# ext.net
KiCad netlist of a schematic drawn in EAGLE
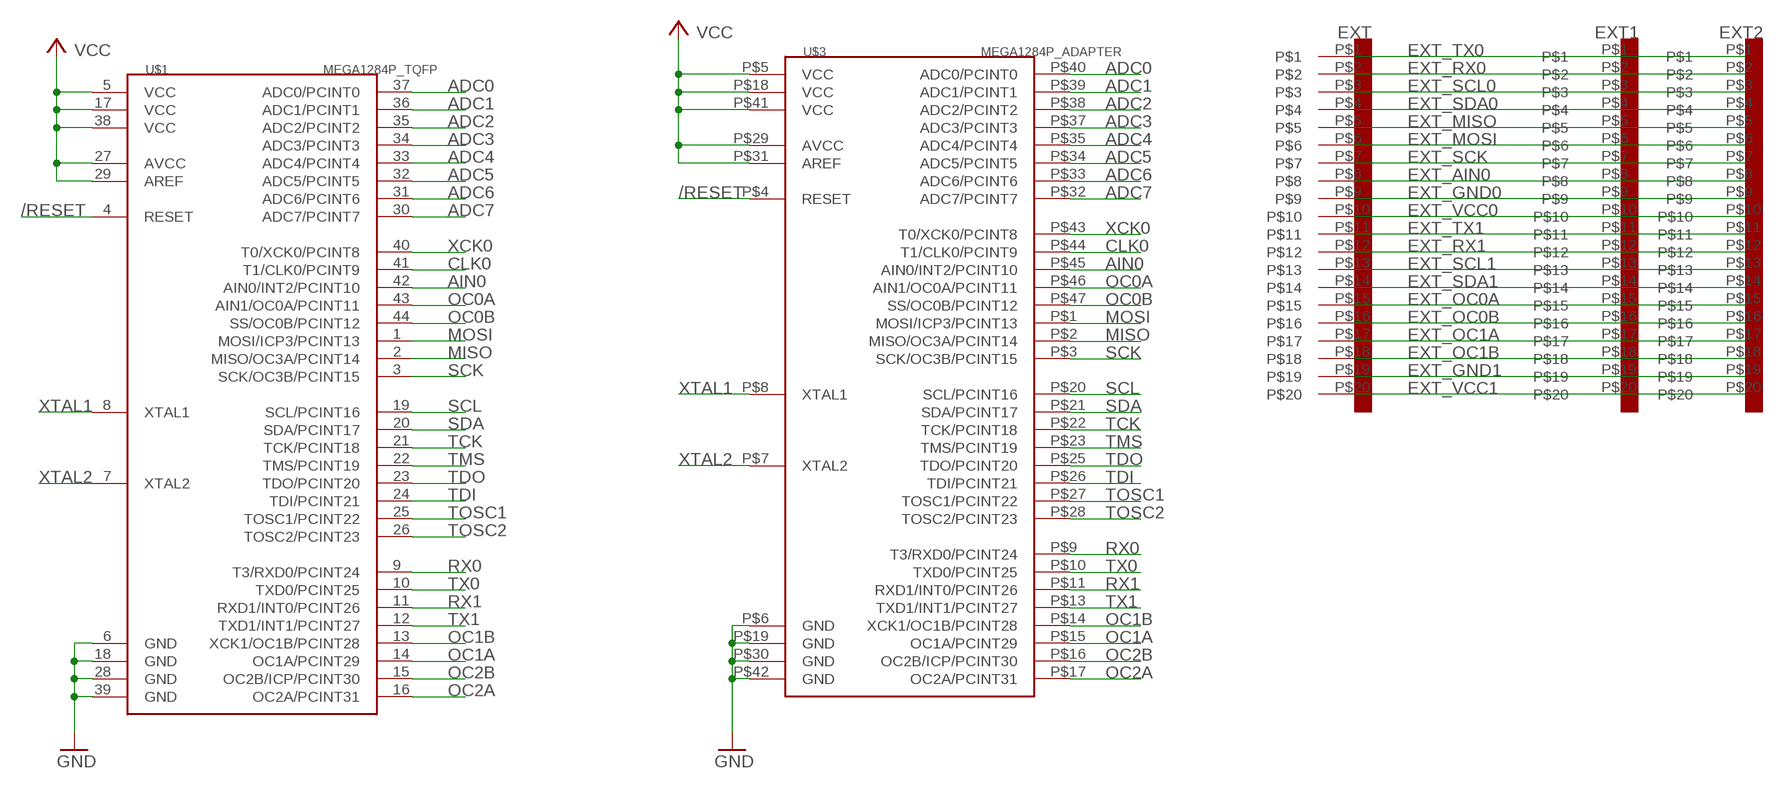
[diagram p0: schematic, sheet 1]

(export (version "E")
  (design (tool "Eeschema 10.0.6"))
  (components
    (comp (ref "EXT")
      (value "CON_DIL_20")
      (footprint "eagle-import:CON_DIL_20")
      (libsource (lib "eagle-import") (part "CON_DIL_20"))
    )
    (comp (ref "EXT1")
      (value "CON_DIL_20")
      (footprint "eagle-import:CON_DIL_20")
      (libsource (lib "eagle-import") (part "CON_DIL_20"))
    )
    (comp (ref "EXT2")
      (value "CON_DIL_20")
      (footprint "eagle-import:CON_DIL_20")
      (libsource (lib "eagle-import") (part "CON_DIL_20"))
    )
    (comp (ref "U$1")
      (value "MEGA1284P_TQFP")
      (footprint "eagle-import:TQFP44")
      (libsource (lib "eagle-import") (part "MEGA1284P_TQFP"))
    )
    (comp (ref "U$3")
      (value "MEGA1284P_ADAPTER")
      (footprint "eagle-import:TQFP44-ADAPTER")
      (libsource (lib "eagle-import") (part "MEGA1284P_ADAPTER"))
    )
  )
  (nets
    (net (code "1") (name "ADC0") (class "Default")
      (node (ref "U$1") (pin "37") (pinfunction "ADC0/PCINT0_37") (pintype "bidirectional"))
      (node (ref "U$3") (pin "P$40") (pinfunction "ADC0/PCINT0_P$40") (pintype "bidirectional"))
    )
    (net (code "2") (name "ADC1") (class "Default")
      (node (ref "U$1") (pin "36") (pinfunction "ADC1/PCINT1_36") (pintype "bidirectional"))
      (node (ref "U$3") (pin "P$39") (pinfunction "ADC1/PCINT1_P$39") (pintype "bidirectional"))
    )
    (net (code "3") (name "ADC2") (class "Default")
      (node (ref "U$1") (pin "35") (pinfunction "ADC2/PCINT2_35") (pintype "bidirectional"))
      (node (ref "U$3") (pin "P$38") (pinfunction "ADC2/PCINT2_P$38") (pintype "bidirectional"))
    )
    (net (code "4") (name "ADC3") (class "Default")
      (node (ref "U$1") (pin "34") (pinfunction "ADC3/PCINT3_34") (pintype "bidirectional"))
      (node (ref "U$3") (pin "P$37") (pinfunction "ADC3/PCINT3_P$37") (pintype "bidirectional"))
    )
    (net (code "5") (name "ADC4") (class "Default")
      (node (ref "U$1") (pin "33") (pinfunction "ADC4/PCINT4_33") (pintype "bidirectional"))
      (node (ref "U$3") (pin "P$35") (pinfunction "ADC4/PCINT4_P$35") (pintype "bidirectional"))
    )
    (net (code "6") (name "ADC5") (class "Default")
      (node (ref "U$1") (pin "32") (pinfunction "ADC5/PCINT5_32") (pintype "bidirectional"))
      (node (ref "U$3") (pin "P$34") (pinfunction "ADC5/PCINT5_P$34") (pintype "bidirectional"))
    )
    (net (code "7") (name "ADC6") (class "Default")
      (node (ref "U$1") (pin "31") (pinfunction "ADC6/PCINT6_31") (pintype "bidirectional"))
      (node (ref "U$3") (pin "P$33") (pinfunction "ADC6/PCINT6_P$33") (pintype "bidirectional"))
    )
    (net (code "8") (name "ADC7") (class "Default")
      (node (ref "U$1") (pin "30") (pinfunction "ADC7/PCINT7_30") (pintype "bidirectional"))
      (node (ref "U$3") (pin "P$32") (pinfunction "ADC7/PCINT7_P$32") (pintype "bidirectional"))
    )
    (net (code "9") (name "AIN0") (class "Default")
      (node (ref "U$1") (pin "42") (pinfunction "AIN0/INT2/PCINT10_42") (pintype "bidirectional"))
      (node (ref "U$3") (pin "P$45") (pinfunction "AIN0/INT2/PCINT10_P$45") (pintype "bidirectional"))
    )
    (net (code "10") (name "CLK0") (class "Default")
      (node (ref "U$1") (pin "41") (pinfunction "T1/CLK0/PCINT9_41") (pintype "bidirectional"))
      (node (ref "U$3") (pin "P$44") (pinfunction "T1/CLK0/PCINT9_P$44") (pintype "bidirectional"))
    )
    (net (code "11") (name "EXT_AIN0") (class "Default")
      (node (ref "EXT") (pin "P$8") (pinfunction "P$8_P$8") (pintype "bidirectional"))
      (node (ref "EXT1") (pin "P$8") (pinfunction "P$8_P$8") (pintype "bidirectional"))
      (node (ref "EXT2") (pin "P$8") (pinfunction "P$8_P$8") (pintype "bidirectional"))
    )
    (net (code "12") (name "EXT_GND0") (class "Default")
      (node (ref "EXT") (pin "P$9") (pinfunction "P$9_P$9") (pintype "bidirectional"))
      (node (ref "EXT1") (pin "P$9") (pinfunction "P$9_P$9") (pintype "bidirectional"))
      (node (ref "EXT2") (pin "P$9") (pinfunction "P$9_P$9") (pintype "bidirectional"))
    )
    (net (code "13") (name "EXT_GND1") (class "Default")
      (node (ref "EXT") (pin "P$19") (pinfunction "P$19_P$19") (pintype "bidirectional"))
      (node (ref "EXT1") (pin "P$19") (pinfunction "P$19_P$19") (pintype "bidirectional"))
      (node (ref "EXT2") (pin "P$19") (pinfunction "P$19_P$19") (pintype "bidirectional"))
    )
    (net (code "14") (name "EXT_MISO") (class "Default")
      (node (ref "EXT") (pin "P$5") (pinfunction "P$5_P$5") (pintype "bidirectional"))
      (node (ref "EXT1") (pin "P$5") (pinfunction "P$5_P$5") (pintype "bidirectional"))
      (node (ref "EXT2") (pin "P$5") (pinfunction "P$5_P$5") (pintype "bidirectional"))
    )
    (net (code "15") (name "EXT_MOSI") (class "Default")
      (node (ref "EXT") (pin "P$6") (pinfunction "P$6_P$6") (pintype "bidirectional"))
      (node (ref "EXT1") (pin "P$6") (pinfunction "P$6_P$6") (pintype "bidirectional"))
      (node (ref "EXT2") (pin "P$6") (pinfunction "P$6_P$6") (pintype "bidirectional"))
    )
    (net (code "16") (name "EXT_OC0A") (class "Default")
      (node (ref "EXT") (pin "P$15") (pinfunction "P$15_P$15") (pintype "bidirectional"))
      (node (ref "EXT1") (pin "P$15") (pinfunction "P$15_P$15") (pintype "bidirectional"))
      (node (ref "EXT2") (pin "P$15") (pinfunction "P$15_P$15") (pintype "bidirectional"))
    )
    (net (code "17") (name "EXT_OC0B") (class "Default")
      (node (ref "EXT") (pin "P$16") (pinfunction "P$16_P$16") (pintype "bidirectional"))
      (node (ref "EXT1") (pin "P$16") (pinfunction "P$16_P$16") (pintype "bidirectional"))
      (node (ref "EXT2") (pin "P$16") (pinfunction "P$16_P$16") (pintype "bidirectional"))
    )
    (net (code "18") (name "EXT_OC1A") (class "Default")
      (node (ref "EXT") (pin "P$17") (pinfunction "P$17_P$17") (pintype "bidirectional"))
      (node (ref "EXT1") (pin "P$17") (pinfunction "P$17_P$17") (pintype "bidirectional"))
      (node (ref "EXT2") (pin "P$17") (pinfunction "P$17_P$17") (pintype "bidirectional"))
    )
    (net (code "19") (name "EXT_OC1B") (class "Default")
      (node (ref "EXT") (pin "P$18") (pinfunction "P$18_P$18") (pintype "bidirectional"))
      (node (ref "EXT1") (pin "P$18") (pinfunction "P$18_P$18") (pintype "bidirectional"))
      (node (ref "EXT2") (pin "P$18") (pinfunction "P$18_P$18") (pintype "bidirectional"))
    )
    (net (code "20") (name "EXT_RX0") (class "Default")
      (node (ref "EXT") (pin "P$2") (pinfunction "P$2_P$2") (pintype "bidirectional"))
      (node (ref "EXT1") (pin "P$2") (pinfunction "P$2_P$2") (pintype "bidirectional"))
      (node (ref "EXT2") (pin "P$2") (pinfunction "P$2_P$2") (pintype "bidirectional"))
    )
    (net (code "21") (name "EXT_RX1") (class "Default")
      (node (ref "EXT") (pin "P$12") (pinfunction "P$12_P$12") (pintype "bidirectional"))
      (node (ref "EXT1") (pin "P$12") (pinfunction "P$12_P$12") (pintype "bidirectional"))
      (node (ref "EXT2") (pin "P$12") (pinfunction "P$12_P$12") (pintype "bidirectional"))
    )
    (net (code "22") (name "EXT_SCK") (class "Default")
      (node (ref "EXT") (pin "P$7") (pinfunction "P$7_P$7") (pintype "bidirectional"))
      (node (ref "EXT1") (pin "P$7") (pinfunction "P$7_P$7") (pintype "bidirectional"))
      (node (ref "EXT2") (pin "P$7") (pinfunction "P$7_P$7") (pintype "bidirectional"))
    )
    (net (code "23") (name "EXT_SCL0") (class "Default")
      (node (ref "EXT") (pin "P$3") (pinfunction "P$3_P$3") (pintype "bidirectional"))
      (node (ref "EXT1") (pin "P$3") (pinfunction "P$3_P$3") (pintype "bidirectional"))
      (node (ref "EXT2") (pin "P$3") (pinfunction "P$3_P$3") (pintype "bidirectional"))
    )
    (net (code "24") (name "EXT_SCL1") (class "Default")
      (node (ref "EXT") (pin "P$13") (pinfunction "P$13_P$13") (pintype "bidirectional"))
      (node (ref "EXT1") (pin "P$13") (pinfunction "P$13_P$13") (pintype "bidirectional"))
      (node (ref "EXT2") (pin "P$13") (pinfunction "P$13_P$13") (pintype "bidirectional"))
    )
    (net (code "25") (name "EXT_SDA0") (class "Default")
      (node (ref "EXT") (pin "P$4") (pinfunction "P$4_P$4") (pintype "bidirectional"))
      (node (ref "EXT1") (pin "P$4") (pinfunction "P$4_P$4") (pintype "bidirectional"))
      (node (ref "EXT2") (pin "P$4") (pinfunction "P$4_P$4") (pintype "bidirectional"))
    )
    (net (code "26") (name "EXT_SDA1") (class "Default")
      (node (ref "EXT") (pin "P$14") (pinfunction "P$14_P$14") (pintype "bidirectional"))
      (node (ref "EXT1") (pin "P$14") (pinfunction "P$14_P$14") (pintype "bidirectional"))
      (node (ref "EXT2") (pin "P$14") (pinfunction "P$14_P$14") (pintype "bidirectional"))
    )
    (net (code "27") (name "EXT_TX0") (class "Default")
      (node (ref "EXT") (pin "P$1") (pinfunction "P$1_P$1") (pintype "bidirectional"))
      (node (ref "EXT1") (pin "P$1") (pinfunction "P$1_P$1") (pintype "bidirectional"))
      (node (ref "EXT2") (pin "P$1") (pinfunction "P$1_P$1") (pintype "bidirectional"))
    )
    (net (code "28") (name "EXT_TX1") (class "Default")
      (node (ref "EXT") (pin "P$11") (pinfunction "P$11_P$11") (pintype "bidirectional"))
      (node (ref "EXT1") (pin "P$11") (pinfunction "P$11_P$11") (pintype "bidirectional"))
      (node (ref "EXT2") (pin "P$11") (pinfunction "P$11_P$11") (pintype "bidirectional"))
    )
    (net (code "29") (name "EXT_VCC0") (class "Default")
      (node (ref "EXT") (pin "P$10") (pinfunction "P$10_P$10") (pintype "bidirectional"))
      (node (ref "EXT1") (pin "P$10") (pinfunction "P$10_P$10") (pintype "bidirectional"))
      (node (ref "EXT2") (pin "P$10") (pinfunction "P$10_P$10") (pintype "bidirectional"))
    )
    (net (code "30") (name "EXT_VCC1") (class "Default")
      (node (ref "EXT") (pin "P$20") (pinfunction "P$20_P$20") (pintype "bidirectional"))
      (node (ref "EXT1") (pin "P$20") (pinfunction "P$20_P$20") (pintype "bidirectional"))
      (node (ref "EXT2") (pin "P$20") (pinfunction "P$20_P$20") (pintype "bidirectional"))
    )
    (net (code "31") (name "GND") (class "Default")
      (node (ref "U$1") (pin "18") (pinfunction "GND_18") (pintype "bidirectional"))
      (node (ref "U$1") (pin "28") (pinfunction "GND_28") (pintype "bidirectional"))
      (node (ref "U$1") (pin "39") (pinfunction "GND_39") (pintype "bidirectional"))
      (node (ref "U$1") (pin "6") (pinfunction "GND_6") (pintype "bidirectional"))
      (node (ref "U$3") (pin "P$19") (pinfunction "GND_P$19") (pintype "bidirectional"))
      (node (ref "U$3") (pin "P$30") (pinfunction "GND_P$30") (pintype "bidirectional"))
      (node (ref "U$3") (pin "P$42") (pinfunction "GND_P$42") (pintype "bidirectional"))
      (node (ref "U$3") (pin "P$6") (pinfunction "GND_P$6") (pintype "bidirectional"))
    )
    (net (code "32") (name "MISO") (class "Default")
      (node (ref "U$1") (pin "2") (pinfunction "MISO/OC3A/PCINT14_2") (pintype "bidirectional"))
      (node (ref "U$3") (pin "P$2") (pinfunction "MISO/OC3A/PCINT14_P$2") (pintype "bidirectional"))
    )
    (net (code "33") (name "MOSI") (class "Default")
      (node (ref "U$1") (pin "1") (pinfunction "MOSI/ICP3/PCINT13_1") (pintype "bidirectional"))
      (node (ref "U$3") (pin "P$1") (pinfunction "MOSI/ICP3/PCINT13_P$1") (pintype "bidirectional"))
    )
    (net (code "34") (name "OC0A") (class "Default")
      (node (ref "U$1") (pin "43") (pinfunction "AIN1/OC0A/PCINT11_43") (pintype "bidirectional"))
      (node (ref "U$3") (pin "P$46") (pinfunction "AIN1/OC0A/PCINT11_P$46") (pintype "bidirectional"))
    )
    (net (code "35") (name "OC0B") (class "Default")
      (node (ref "U$1") (pin "44") (pinfunction "SS/OC0B/PCINT12_44") (pintype "bidirectional"))
      (node (ref "U$3") (pin "P$47") (pinfunction "SS/OC0B/PCINT12_P$47") (pintype "bidirectional"))
    )
    (net (code "36") (name "OC1A") (class "Default")
      (node (ref "U$1") (pin "14") (pinfunction "OC1A/PCINT29_14") (pintype "bidirectional"))
      (node (ref "U$3") (pin "P$15") (pinfunction "OC1A/PCINT29_P$15") (pintype "bidirectional"))
    )
    (net (code "37") (name "OC1B") (class "Default")
      (node (ref "U$1") (pin "13") (pinfunction "XCK1/OC1B/PCINT28_13") (pintype "bidirectional"))
      (node (ref "U$3") (pin "P$14") (pinfunction "XCK1/OC1B/PCINT28_P$14") (pintype "bidirectional"))
    )
    (net (code "38") (name "OC2A") (class "Default")
      (node (ref "U$1") (pin "16") (pinfunction "OC2A/PCINT31_16") (pintype "bidirectional"))
      (node (ref "U$3") (pin "P$17") (pinfunction "OC2A/PCINT31_P$17") (pintype "bidirectional"))
    )
    (net (code "39") (name "OC2B") (class "Default")
      (node (ref "U$1") (pin "15") (pinfunction "OC2B/ICP/PCINT30_15") (pintype "bidirectional"))
      (node (ref "U$3") (pin "P$16") (pinfunction "OC2B/ICP/PCINT30_P$16") (pintype "bidirectional"))
    )
    (net (code "40") (name "RX0") (class "Default")
      (node (ref "U$1") (pin "9") (pinfunction "T3/RXD0/PCINT24_9") (pintype "bidirectional"))
      (node (ref "U$3") (pin "P$9") (pinfunction "T3/RXD0/PCINT24_P$9") (pintype "bidirectional"))
    )
    (net (code "41") (name "RX1") (class "Default")
      (node (ref "U$1") (pin "11") (pinfunction "RXD1/INT0/PCINT26_11") (pintype "bidirectional"))
      (node (ref "U$3") (pin "P$11") (pinfunction "RXD1/INT0/PCINT26_P$11") (pintype "bidirectional"))
    )
    (net (code "42") (name "SCK") (class "Default")
      (node (ref "U$1") (pin "3") (pinfunction "SCK/OC3B/PCINT15_3") (pintype "bidirectional"))
      (node (ref "U$3") (pin "P$3") (pinfunction "SCK/OC3B/PCINT15_P$3") (pintype "bidirectional"))
    )
    (net (code "43") (name "SCL") (class "Default")
      (node (ref "U$1") (pin "19") (pinfunction "SCL/PCINT16_19") (pintype "bidirectional"))
      (node (ref "U$3") (pin "P$20") (pinfunction "SCL/PCINT16_P$20") (pintype "bidirectional"))
    )
    (net (code "44") (name "SDA") (class "Default")
      (node (ref "U$1") (pin "20") (pinfunction "SDA/PCINT17_20") (pintype "bidirectional"))
      (node (ref "U$3") (pin "P$21") (pinfunction "SDA/PCINT17_P$21") (pintype "bidirectional"))
    )
    (net (code "45") (name "TCK") (class "Default")
      (node (ref "U$1") (pin "21") (pinfunction "TCK/PCINT18_21") (pintype "bidirectional"))
      (node (ref "U$3") (pin "P$22") (pinfunction "TCK/PCINT18_P$22") (pintype "bidirectional"))
    )
    (net (code "46") (name "TDI") (class "Default")
      (node (ref "U$1") (pin "24") (pinfunction "TDI/PCINT21_24") (pintype "bidirectional"))
      (node (ref "U$3") (pin "P$26") (pinfunction "TDI/PCINT21_P$26") (pintype "bidirectional"))
    )
    (net (code "47") (name "TDO") (class "Default")
      (node (ref "U$1") (pin "23") (pinfunction "TDO/PCINT20_23") (pintype "bidirectional"))
      (node (ref "U$3") (pin "P$25") (pinfunction "TDO/PCINT20_P$25") (pintype "bidirectional"))
    )
    (net (code "48") (name "TMS") (class "Default")
      (node (ref "U$1") (pin "22") (pinfunction "TMS/PCINT19_22") (pintype "bidirectional"))
      (node (ref "U$3") (pin "P$23") (pinfunction "TMS/PCINT19_P$23") (pintype "bidirectional"))
    )
    (net (code "49") (name "TOSC1") (class "Default")
      (node (ref "U$1") (pin "25") (pinfunction "TOSC1/PCINT22_25") (pintype "bidirectional"))
      (node (ref "U$3") (pin "P$27") (pinfunction "TOSC1/PCINT22_P$27") (pintype "bidirectional"))
    )
    (net (code "50") (name "TOSC2") (class "Default")
      (node (ref "U$1") (pin "26") (pinfunction "TOSC2/PCINT23_26") (pintype "bidirectional"))
      (node (ref "U$3") (pin "P$28") (pinfunction "TOSC2/PCINT23_P$28") (pintype "bidirectional"))
    )
    (net (code "51") (name "TX0") (class "Default")
      (node (ref "U$1") (pin "10") (pinfunction "TXD0/PCINT25_10") (pintype "bidirectional"))
      (node (ref "U$3") (pin "P$10") (pinfunction "TXD0/PCINT25_P$10") (pintype "bidirectional"))
    )
    (net (code "52") (name "TX1") (class "Default")
      (node (ref "U$1") (pin "12") (pinfunction "TXD1/INT1/PCINT27_12") (pintype "bidirectional"))
      (node (ref "U$3") (pin "P$13") (pinfunction "TXD1/INT1/PCINT27_P$13") (pintype "bidirectional"))
    )
    (net (code "53") (name "VCC") (class "Default")
      (node (ref "U$1") (pin "17") (pinfunction "VCC_17") (pintype "bidirectional"))
      (node (ref "U$1") (pin "27") (pinfunction "AVCC_27") (pintype "bidirectional"))
      (node (ref "U$1") (pin "29") (pinfunction "AREF_29") (pintype "bidirectional"))
      (node (ref "U$1") (pin "38") (pinfunction "VCC_38") (pintype "bidirectional"))
      (node (ref "U$1") (pin "5") (pinfunction "VCC_5") (pintype "bidirectional"))
      (node (ref "U$3") (pin "P$18") (pinfunction "VCC_P$18") (pintype "bidirectional"))
      (node (ref "U$3") (pin "P$29") (pinfunction "AVCC_P$29") (pintype "bidirectional"))
      (node (ref "U$3") (pin "P$31") (pinfunction "AREF_P$31") (pintype "bidirectional"))
      (node (ref "U$3") (pin "P$41") (pinfunction "VCC_P$41") (pintype "bidirectional"))
      (node (ref "U$3") (pin "P$5") (pinfunction "VCC_P$5") (pintype "bidirectional"))
    )
    (net (code "54") (name "XCK0") (class "Default")
      (node (ref "U$1") (pin "40") (pinfunction "T0/XCK0/PCINT8_40") (pintype "bidirectional"))
      (node (ref "U$3") (pin "P$43") (pinfunction "T0/XCK0/PCINT8_P$43") (pintype "bidirectional"))
    )
    (net (code "55") (name "XTAL1") (class "Default")
      (node (ref "U$1") (pin "8") (pinfunction "XTAL1_8") (pintype "bidirectional"))
      (node (ref "U$3") (pin "P$8") (pinfunction "XTAL1_P$8") (pintype "bidirectional"))
    )
    (net (code "56") (name "XTAL2") (class "Default")
      (node (ref "U$1") (pin "7") (pinfunction "XTAL2_7") (pintype "bidirectional"))
      (node (ref "U$3") (pin "P$7") (pinfunction "XTAL2_P$7") (pintype "bidirectional"))
    )
    (net (code "57") (name "{slash}RESET") (class "Default")
      (node (ref "U$1") (pin "4") (pinfunction "RESET_4") (pintype "bidirectional"))
      (node (ref "U$3") (pin "P$4") (pinfunction "RESET_P$4") (pintype "bidirectional"))
    )
  )
)
